# FT232_USB_UART_power.net
KiCad netlist of a schematic drawn in EAGLE
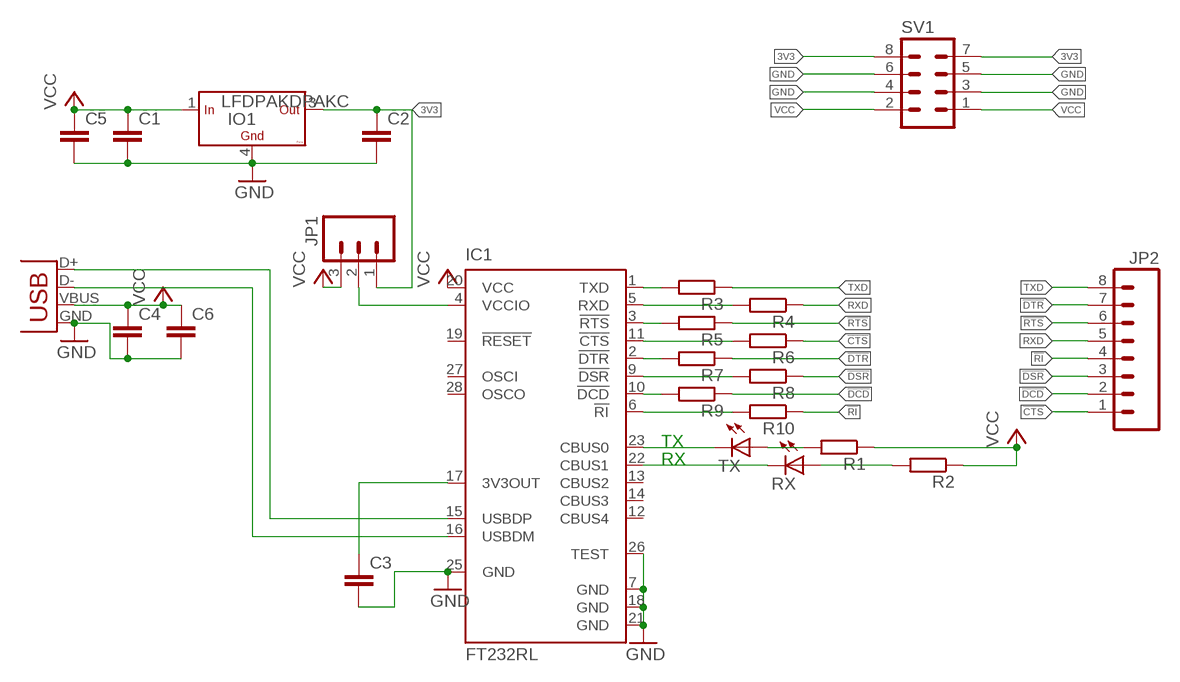
[diagram p0: schematic, sheet 1]

(export (version "E")
  (design (tool "Eeschema 10.0.6"))
  (components
    (comp (ref "C1")
      (value "C-EUC0805")
      (footprint "eagle-import:C0805")
      (libsource (lib "eagle-import") (part "C-EUC0805"))
    )
    (comp (ref "C2")
      (value "C-EUC0805")
      (footprint "eagle-import:C0805")
      (libsource (lib "eagle-import") (part "C-EUC0805"))
    )
    (comp (ref "C3")
      (value "C-EUC0805")
      (footprint "eagle-import:C0805")
      (libsource (lib "eagle-import") (part "C-EUC0805"))
    )
    (comp (ref "C4")
      (value "C-EUC0805")
      (footprint "eagle-import:C0805")
      (libsource (lib "eagle-import") (part "C-EUC0805"))
    )
    (comp (ref "C5")
      (value "C-EUC0805")
      (footprint "eagle-import:C0805")
      (libsource (lib "eagle-import") (part "C-EUC0805"))
    )
    (comp (ref "C6")
      (value "C-EUC0805")
      (footprint "eagle-import:C0805")
      (libsource (lib "eagle-import") (part "C-EUC0805"))
    )
    (comp (ref "IC1")
      (value "FT232RL")
      (footprint "eagle-import:SSOP28")
      (libsource (lib "eagle-import") (part "FT232RL"))
    )
    (comp (ref "IO1")
      (value "LFDPAKDPAKC")
      (footprint "eagle-import:DPAK")
      (libsource (lib "eagle-import") (part "LF??CDPAK"))
    )
    (comp (ref "JP1")
      (value "M03LONGPADS")
      (footprint "eagle-import:1X03_LONGPADS")
      (libsource (lib "eagle-import") (part "M03LONGPADS"))
    )
    (comp (ref "JP2")
      (value "M08LONGPADS")
      (footprint "eagle-import:1X08_LONGPADS")
      (libsource (lib "eagle-import") (part "M08LONGPADS"))
    )
    (comp (ref "R1")
      (value "R-EU_M0805")
      (footprint "eagle-import:M0805")
      (libsource (lib "eagle-import") (part "R-EU_M0805"))
    )
    (comp (ref "R2")
      (value "R-EU_M0805")
      (footprint "eagle-import:M0805")
      (libsource (lib "eagle-import") (part "R-EU_M0805"))
    )
    (comp (ref "R3")
      (value "R-EU_M0805")
      (footprint "eagle-import:M0805")
      (libsource (lib "eagle-import") (part "R-EU_M0805"))
    )
    (comp (ref "R4")
      (value "R-EU_M0805")
      (footprint "eagle-import:M0805")
      (libsource (lib "eagle-import") (part "R-EU_M0805"))
    )
    (comp (ref "R5")
      (value "R-EU_M0805")
      (footprint "eagle-import:M0805")
      (libsource (lib "eagle-import") (part "R-EU_M0805"))
    )
    (comp (ref "R6")
      (value "R-EU_M0805")
      (footprint "eagle-import:M0805")
      (libsource (lib "eagle-import") (part "R-EU_M0805"))
    )
    (comp (ref "R7")
      (value "R-EU_M0805")
      (footprint "eagle-import:M0805")
      (libsource (lib "eagle-import") (part "R-EU_M0805"))
    )
    (comp (ref "R8")
      (value "R-EU_M0805")
      (footprint "eagle-import:M0805")
      (libsource (lib "eagle-import") (part "R-EU_M0805"))
    )
    (comp (ref "R9")
      (value "R-EU_M0805")
      (footprint "eagle-import:M0805")
      (libsource (lib "eagle-import") (part "R-EU_M0805"))
    )
    (comp (ref "R10")
      (value "R-EU_M0805")
      (footprint "eagle-import:M0805")
      (libsource (lib "eagle-import") (part "R-EU_M0805"))
    )
    (comp (ref "RX")
      (value "LEDSML0805")
      (footprint "eagle-import:SML0805")
      (libsource (lib "eagle-import") (part "LEDSML0805"))
    )
    (comp (ref "SV1")
      (value "MA04-2")
      (footprint "eagle-import:MA04-2")
      (libsource (lib "eagle-import") (part "MA04-2"))
    )
    (comp (ref "TX")
      (value "LEDSML0805")
      (footprint "eagle-import:SML0805")
      (libsource (lib "eagle-import") (part "LEDSML0805"))
    )
    (comp (ref "X1")
      (value "USB-SMD-NS")
      (footprint "eagle-import:USB-MINIB-NOSTOP")
      (libsource (lib "eagle-import") (part "USB-SMD-NS"))
    )
  )
  (nets
    (net (code "1") (name "/~{CTS}") (class "Default")
      (node (ref "JP2") (pin "1") (pinfunction "1_1") (pintype "passive"))
      (node (ref "R6") (pin "1") (pinfunction "1_1") (pintype "passive"))
    )
    (net (code "2") (name "/~{DCD}") (class "Default")
      (node (ref "JP2") (pin "2") (pinfunction "2_2") (pintype "passive"))
      (node (ref "R9") (pin "1") (pinfunction "1_1") (pintype "passive"))
    )
    (net (code "3") (name "/~{DSR}") (class "Default")
      (node (ref "JP2") (pin "3") (pinfunction "3_3") (pintype "passive"))
      (node (ref "R8") (pin "1") (pinfunction "1_1") (pintype "passive"))
    )
    (net (code "4") (name "/~{DTR}") (class "Default")
      (node (ref "JP2") (pin "7") (pinfunction "7_7") (pintype "passive"))
      (node (ref "R7") (pin "1") (pinfunction "1_1") (pintype "passive"))
    )
    (net (code "5") (name "/~{RI}") (class "Default")
      (node (ref "JP2") (pin "4") (pinfunction "4_4") (pintype "passive"))
      (node (ref "R10") (pin "1") (pinfunction "1_1") (pintype "passive"))
    )
    (net (code "6") (name "/~{RTS}") (class "Default")
      (node (ref "JP2") (pin "6") (pinfunction "6_6") (pintype "passive"))
      (node (ref "R5") (pin "1") (pinfunction "1_1") (pintype "passive"))
    )
    (net (code "7") (name "3V3") (class "Default")
      (node (ref "C2") (pin "1") (pinfunction "1_1") (pintype "passive"))
      (node (ref "IO1") (pin "3") (pinfunction "OUT_3") (pintype "passive"))
      (node (ref "JP1") (pin "1") (pinfunction "1_1") (pintype "passive"))
      (node (ref "SV1") (pin "7") (pinfunction "7_7") (pintype "passive"))
      (node (ref "SV1") (pin "8") (pinfunction "8_8") (pintype "passive"))
    )
    (net (code "8") (name "GND") (class "Default")
      (node (ref "C1") (pin "2") (pinfunction "2_2") (pintype "passive"))
      (node (ref "C2") (pin "2") (pinfunction "2_2") (pintype "passive"))
      (node (ref "C3") (pin "2") (pinfunction "2_2") (pintype "passive"))
      (node (ref "C4") (pin "2") (pinfunction "2_2") (pintype "passive"))
      (node (ref "C5") (pin "2") (pinfunction "2_2") (pintype "passive"))
      (node (ref "C6") (pin "2") (pinfunction "2_2") (pintype "passive"))
      (node (ref "IC1") (pin "18") (pinfunction "GND_18") (pintype "power_in"))
      (node (ref "IC1") (pin "21") (pinfunction "GND_21") (pintype "power_in"))
      (node (ref "IC1") (pin "25") (pinfunction "GND_25") (pintype "power_in"))
      (node (ref "IC1") (pin "26") (pinfunction "TEST_26") (pintype "input"))
      (node (ref "IC1") (pin "7") (pinfunction "GND_7") (pintype "power_in"))
      (node (ref "IO1") (pin "4") (pinfunction "GND_4") (pintype "passive"))
      (node (ref "SV1") (pin "3") (pinfunction "3_3") (pintype "passive"))
      (node (ref "SV1") (pin "4") (pinfunction "4_4") (pintype "passive"))
      (node (ref "SV1") (pin "5") (pinfunction "5_5") (pintype "passive"))
      (node (ref "SV1") (pin "6") (pinfunction "6_6") (pintype "passive"))
      (node (ref "X1") (pin "GND") (pinfunction "GND_GND") (pintype "bidirectional"))
    )
    (net (code "9") (name "Net-(IC1-3V3OUT)") (class "Default")
      (node (ref "C3") (pin "1") (pinfunction "1_1") (pintype "passive"))
      (node (ref "IC1") (pin "17") (pinfunction "3V3OUT_17") (pintype "output"))
    )
    (net (code "10") (name "Net-(IC1-CBUS0)") (class "Default")
      (node (ref "IC1") (pin "23") (pinfunction "CBUS0_23") (pintype "bidirectional"))
      (node (ref "TX") (pin "C") (pinfunction "C_C") (pintype "passive"))
    )
    (net (code "11") (name "Net-(IC1-CBUS1)") (class "Default")
      (node (ref "IC1") (pin "22") (pinfunction "CBUS1_22") (pintype "bidirectional"))
      (node (ref "RX") (pin "C") (pinfunction "C_C") (pintype "passive"))
    )
    (net (code "12") (name "Net-(IC1-RXD)") (class "Default")
      (node (ref "IC1") (pin "5") (pinfunction "RXD_5") (pintype "input"))
      (node (ref "R4") (pin "2") (pinfunction "2_2") (pintype "passive"))
    )
    (net (code "13") (name "Net-(IC1-TXD)") (class "Default")
      (node (ref "IC1") (pin "1") (pinfunction "TXD_1") (pintype "output"))
      (node (ref "R3") (pin "2") (pinfunction "2_2") (pintype "passive"))
    )
    (net (code "14") (name "Net-(IC1-USBDM)") (class "Default")
      (node (ref "IC1") (pin "16") (pinfunction "USBDM_16") (pintype "bidirectional"))
      (node (ref "X1") (pin "D-") (pinfunction "D-_D-") (pintype "bidirectional"))
    )
    (net (code "15") (name "Net-(IC1-USBDP)") (class "Default")
      (node (ref "IC1") (pin "15") (pinfunction "USBDP_15") (pintype "bidirectional"))
      (node (ref "X1") (pin "D+") (pinfunction "D+_D+") (pintype "bidirectional"))
    )
    (net (code "16") (name "Net-(IC1-VCCIO)") (class "Default")
      (node (ref "IC1") (pin "4") (pinfunction "VCCIO_4") (pintype "power_in"))
      (node (ref "JP1") (pin "2") (pinfunction "2_2") (pintype "passive"))
    )
    (net (code "17") (name "Net-(IC1-~{CTS})") (class "Default")
      (node (ref "IC1") (pin "11") (pinfunction "~{CTS}_11") (pintype "input"))
      (node (ref "R6") (pin "2") (pinfunction "2_2") (pintype "passive"))
    )
    (net (code "18") (name "Net-(IC1-~{DCD})") (class "Default")
      (node (ref "IC1") (pin "10") (pinfunction "~{DCD}_10") (pintype "input"))
      (node (ref "R9") (pin "2") (pinfunction "2_2") (pintype "passive"))
    )
    (net (code "19") (name "Net-(IC1-~{DSR})") (class "Default")
      (node (ref "IC1") (pin "9") (pinfunction "~{DSR}_9") (pintype "input"))
      (node (ref "R8") (pin "2") (pinfunction "2_2") (pintype "passive"))
    )
    (net (code "20") (name "Net-(IC1-~{DTR})") (class "Default")
      (node (ref "IC1") (pin "2") (pinfunction "~{DTR}_2") (pintype "output"))
      (node (ref "R7") (pin "2") (pinfunction "2_2") (pintype "passive"))
    )
    (net (code "21") (name "Net-(IC1-~{RI})") (class "Default")
      (node (ref "IC1") (pin "6") (pinfunction "~{RI}_6") (pintype "input"))
      (node (ref "R10") (pin "2") (pinfunction "2_2") (pintype "passive"))
    )
    (net (code "22") (name "Net-(IC1-~{RTS})") (class "Default")
      (node (ref "IC1") (pin "3") (pinfunction "~{RTS}_3") (pintype "output"))
      (node (ref "R5") (pin "2") (pinfunction "2_2") (pintype "passive"))
    )
    (net (code "23") (name "Net-(R1-Pad2)") (class "Default")
      (node (ref "R1") (pin "2") (pinfunction "2_2") (pintype "passive"))
      (node (ref "TX") (pin "A") (pinfunction "A_A") (pintype "passive"))
    )
    (net (code "24") (name "Net-(R2-Pad2)") (class "Default")
      (node (ref "R2") (pin "2") (pinfunction "2_2") (pintype "passive"))
      (node (ref "RX") (pin "A") (pinfunction "A_A") (pintype "passive"))
    )
    (net (code "25") (name "RXD") (class "Default")
      (node (ref "JP2") (pin "5") (pinfunction "5_5") (pintype "passive"))
      (node (ref "R4") (pin "1") (pinfunction "1_1") (pintype "passive"))
    )
    (net (code "26") (name "TXD") (class "Default")
      (node (ref "JP2") (pin "8") (pinfunction "8_8") (pintype "passive"))
      (node (ref "R3") (pin "1") (pinfunction "1_1") (pintype "passive"))
    )
    (net (code "27") (name "VCC") (class "Default")
      (node (ref "C1") (pin "1") (pinfunction "1_1") (pintype "passive"))
      (node (ref "C4") (pin "1") (pinfunction "1_1") (pintype "passive"))
      (node (ref "C5") (pin "1") (pinfunction "1_1") (pintype "passive"))
      (node (ref "C6") (pin "1") (pinfunction "1_1") (pintype "passive"))
      (node (ref "IC1") (pin "20") (pinfunction "VCC_20") (pintype "power_in"))
      (node (ref "IO1") (pin "1") (pinfunction "IN_1") (pintype "passive"))
      (node (ref "JP1") (pin "3") (pinfunction "3_3") (pintype "passive"))
      (node (ref "R1") (pin "1") (pinfunction "1_1") (pintype "passive"))
      (node (ref "R2") (pin "1") (pinfunction "1_1") (pintype "passive"))
      (node (ref "SV1") (pin "1") (pinfunction "1_1") (pintype "passive"))
      (node (ref "SV1") (pin "2") (pinfunction "2_2") (pintype "passive"))
      (node (ref "X1") (pin "VBUS") (pinfunction "VBUS_VBUS") (pintype "bidirectional"))
    )
    (net (code "28") (name "unconnected-(IC1-CBUS2-Pad13)") (class "Default")
      (node (ref "IC1") (pin "13") (pinfunction "CBUS2_13") (pintype "bidirectional"))
    )
    (net (code "29") (name "unconnected-(IC1-CBUS3-Pad14)") (class "Default")
      (node (ref "IC1") (pin "14") (pinfunction "CBUS3_14") (pintype "bidirectional"))
    )
    (net (code "30") (name "unconnected-(IC1-CBUS4-Pad12)") (class "Default")
      (node (ref "IC1") (pin "12") (pinfunction "CBUS4_12") (pintype "bidirectional"))
    )
    (net (code "31") (name "unconnected-(IC1-OSCI-Pad27)") (class "Default")
      (node (ref "IC1") (pin "27") (pinfunction "OSCI_27") (pintype "input"))
    )
    (net (code "32") (name "unconnected-(IC1-OSCO-Pad28)") (class "Default")
      (node (ref "IC1") (pin "28") (pinfunction "OSCO_28") (pintype "output"))
    )
    (net (code "33") (name "unconnected-(IC1-~{RESET}-Pad19)") (class "Default")
      (node (ref "IC1") (pin "19") (pinfunction "~{RESET}_19") (pintype "input"))
    )
  )
)
